# lego_motors_booster_1x4-.net
KiCad netlist of a schematic drawn in EAGLE
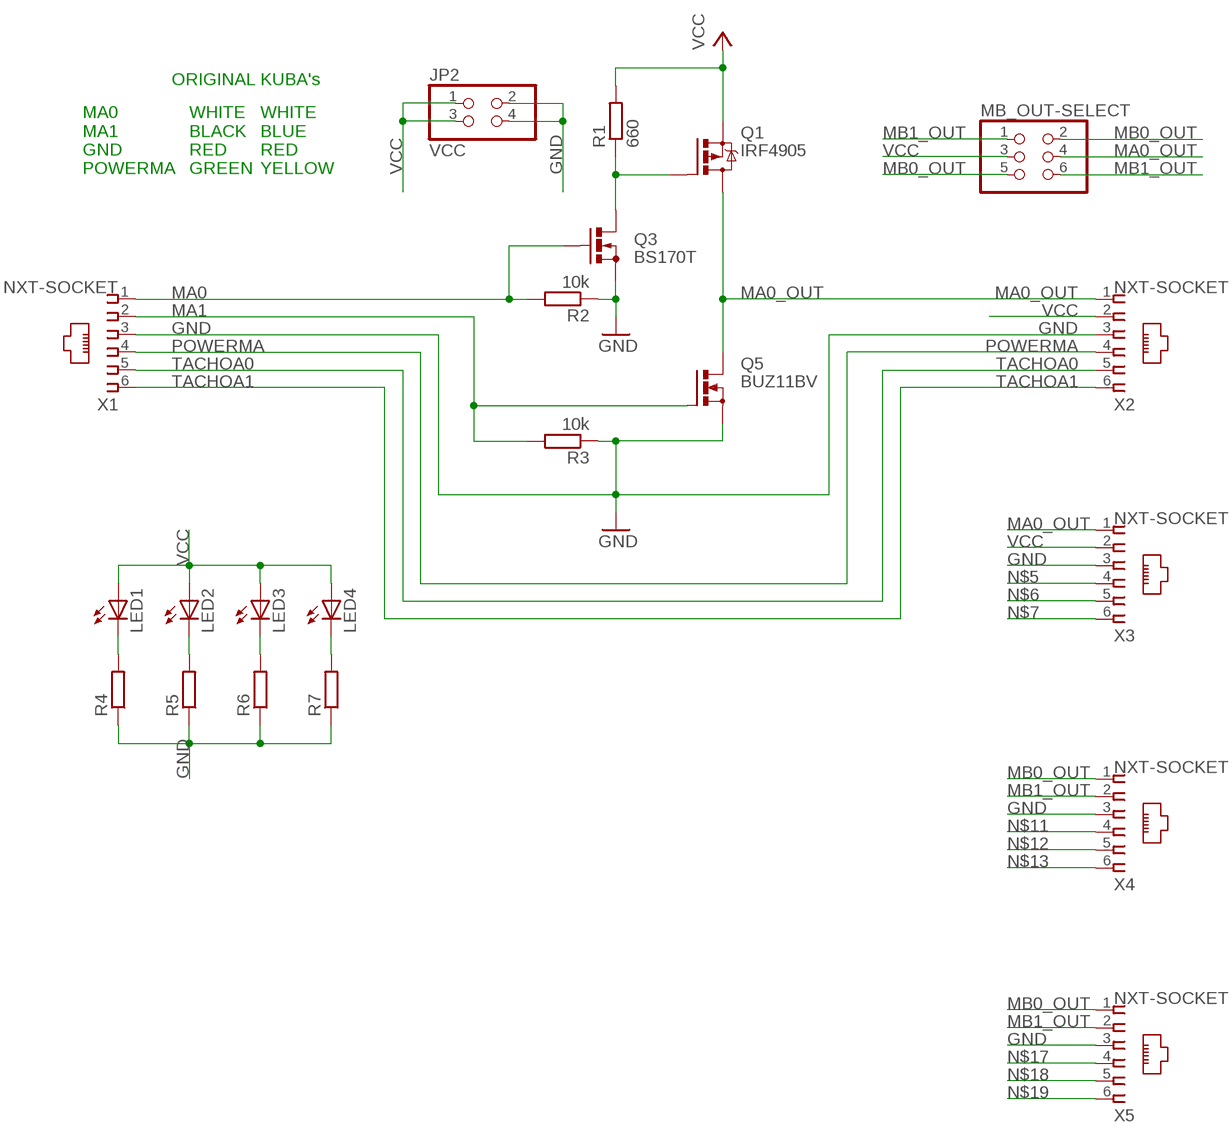
[diagram p0: schematic, sheet 1]

(export (version "E")
  (design (tool "Eeschema 10.0.6"))
  (components
    (comp (ref "JP2")
      (value "VCC")
      (footprint "eagle-import:2X02")
      (libsource (lib "eagle-import") (part "PINHD-2X2"))
    )
    (comp (ref "LED1")
      (value "LEDSML0603")
      (footprint "eagle-import:SML0603")
      (libsource (lib "eagle-import") (part "LEDSML0603"))
    )
    (comp (ref "LED2")
      (value "LEDSML0603")
      (footprint "eagle-import:SML0603")
      (libsource (lib "eagle-import") (part "LEDSML0603"))
    )
    (comp (ref "LED3")
      (value "LEDSML0603")
      (footprint "eagle-import:SML0603")
      (libsource (lib "eagle-import") (part "LEDSML0603"))
    )
    (comp (ref "LED4")
      (value "LEDSML0603")
      (footprint "eagle-import:SML0603")
      (libsource (lib "eagle-import") (part "LEDSML0603"))
    )
    (comp (ref "MB_OUT-SELECT")
      (value "PINHD-2X3")
      (footprint "eagle-import:2X03")
      (libsource (lib "eagle-import") (part "PINHD-2X3"))
    )
    (comp (ref "Q1")
      (value "IRF4905")
      (footprint "eagle-import:TO220BV")
      (libsource (lib "eagle-import") (part "IRF9530"))
    )
    (comp (ref "Q3")
      (value "BS170T")
      (footprint "eagle-import:SOT54E")
      (libsource (lib "eagle-import") (part "BS170T"))
    )
    (comp (ref "Q5")
      (value "BUZ11BV")
      (footprint "eagle-import:TO220BV")
      (libsource (lib "eagle-import") (part "BUZ11BV"))
    )
    (comp (ref "R1")
      (value "660")
      (footprint "eagle-import:0204_7")
      (libsource (lib "eagle-import") (part "R-EU_0204/7"))
    )
    (comp (ref "R2")
      (value "10k")
      (footprint "eagle-import:0204_7")
      (libsource (lib "eagle-import") (part "R-EU_0204/7"))
    )
    (comp (ref "R3")
      (value "10k")
      (footprint "eagle-import:0204_7")
      (libsource (lib "eagle-import") (part "R-EU_0204/7"))
    )
    (comp (ref "R4")
      (value "R-EU_R0603")
      (footprint "eagle-import:R0603")
      (libsource (lib "eagle-import") (part "R-EU_R0603"))
    )
    (comp (ref "R5")
      (value "R-EU_R0603")
      (footprint "eagle-import:R0603")
      (libsource (lib "eagle-import") (part "R-EU_R0603"))
    )
    (comp (ref "R6")
      (value "R-EU_R0603")
      (footprint "eagle-import:R0603")
      (libsource (lib "eagle-import") (part "R-EU_R0603"))
    )
    (comp (ref "R7")
      (value "R-EU_R0603")
      (footprint "eagle-import:R0603")
      (libsource (lib "eagle-import") (part "R-EU_R0603"))
    )
    (comp (ref "X1")
      (value "NXT-SOCKET")
      (footprint "eagle-import:NXT-SOCKET")
      (libsource (lib "eagle-import") (part "NXT-SOCKET"))
    )
    (comp (ref "X2")
      (value "NXT-SOCKET")
      (footprint "eagle-import:NXT-SOCKET")
      (libsource (lib "eagle-import") (part "NXT-SOCKET"))
    )
    (comp (ref "X3")
      (value "NXT-SOCKET")
      (footprint "eagle-import:NXT-SOCKET")
      (libsource (lib "eagle-import") (part "NXT-SOCKET"))
    )
    (comp (ref "X4")
      (value "NXT-SOCKET")
      (footprint "eagle-import:NXT-SOCKET")
      (libsource (lib "eagle-import") (part "NXT-SOCKET"))
    )
    (comp (ref "X5")
      (value "NXT-SOCKET")
      (footprint "eagle-import:NXT-SOCKET")
      (libsource (lib "eagle-import") (part "NXT-SOCKET"))
    )
  )
  (nets
    (net (code "1") (name "/MA0") (class "Default")
      (node (ref "Q3") (pin "G") (pinfunction "G_G") (pintype "passive"))
      (node (ref "R2") (pin "2") (pinfunction "2_2") (pintype "passive"))
      (node (ref "X1") (pin "1") (pinfunction "1_1") (pintype "passive"))
    )
    (net (code "2") (name "/MA0_OUT") (class "Default")
      (node (ref "MB_OUT-SELECT") (pin "4") (pinfunction "4_4") (pintype "passive"))
      (node (ref "Q1") (pin "D") (pinfunction "D_D") (pintype "passive"))
      (node (ref "Q5") (pin "D") (pinfunction "D_D") (pintype "passive"))
      (node (ref "X2") (pin "1") (pinfunction "1_1") (pintype "passive"))
      (node (ref "X3") (pin "1") (pinfunction "1_1") (pintype "passive"))
    )
    (net (code "3") (name "/MA1") (class "Default")
      (node (ref "Q5") (pin "G") (pinfunction "G_G") (pintype "passive"))
      (node (ref "R3") (pin "2") (pinfunction "2_2") (pintype "passive"))
      (node (ref "X1") (pin "2") (pinfunction "2_2") (pintype "passive"))
    )
    (net (code "4") (name "/MB0_OUT") (class "Default")
      (node (ref "MB_OUT-SELECT") (pin "2") (pinfunction "2_2") (pintype "passive"))
      (node (ref "MB_OUT-SELECT") (pin "5") (pinfunction "5_5") (pintype "passive"))
      (node (ref "X4") (pin "1") (pinfunction "1_1") (pintype "passive"))
      (node (ref "X5") (pin "1") (pinfunction "1_1") (pintype "passive"))
    )
    (net (code "5") (name "/MB1_OUT") (class "Default")
      (node (ref "MB_OUT-SELECT") (pin "1") (pinfunction "1_1") (pintype "passive"))
      (node (ref "MB_OUT-SELECT") (pin "6") (pinfunction "6_6") (pintype "passive"))
      (node (ref "X4") (pin "2") (pinfunction "2_2") (pintype "passive"))
      (node (ref "X5") (pin "2") (pinfunction "2_2") (pintype "passive"))
    )
    (net (code "6") (name "/N$5") (class "Default")
      (node (ref "X3") (pin "4") (pinfunction "4_4") (pintype "passive"))
    )
    (net (code "7") (name "/N$6") (class "Default")
      (node (ref "X3") (pin "5") (pinfunction "5_5") (pintype "passive"))
    )
    (net (code "8") (name "/N$7") (class "Default")
      (node (ref "X3") (pin "6") (pinfunction "6_6") (pintype "passive"))
    )
    (net (code "9") (name "/N$11") (class "Default")
      (node (ref "X4") (pin "4") (pinfunction "4_4") (pintype "passive"))
    )
    (net (code "10") (name "/N$12") (class "Default")
      (node (ref "X4") (pin "5") (pinfunction "5_5") (pintype "passive"))
    )
    (net (code "11") (name "/N$13") (class "Default")
      (node (ref "X4") (pin "6") (pinfunction "6_6") (pintype "passive"))
    )
    (net (code "12") (name "/N$17") (class "Default")
      (node (ref "X5") (pin "4") (pinfunction "4_4") (pintype "passive"))
    )
    (net (code "13") (name "/N$18") (class "Default")
      (node (ref "X5") (pin "5") (pinfunction "5_5") (pintype "passive"))
    )
    (net (code "14") (name "/N$19") (class "Default")
      (node (ref "X5") (pin "6") (pinfunction "6_6") (pintype "passive"))
    )
    (net (code "15") (name "/POWERMA") (class "Default")
      (node (ref "X1") (pin "4") (pinfunction "4_4") (pintype "passive"))
      (node (ref "X2") (pin "4") (pinfunction "4_4") (pintype "passive"))
    )
    (net (code "16") (name "/TACHOA0") (class "Default")
      (node (ref "X1") (pin "5") (pinfunction "5_5") (pintype "passive"))
      (node (ref "X2") (pin "5") (pinfunction "5_5") (pintype "passive"))
    )
    (net (code "17") (name "/TACHOA1") (class "Default")
      (node (ref "X1") (pin "6") (pinfunction "6_6") (pintype "passive"))
      (node (ref "X2") (pin "6") (pinfunction "6_6") (pintype "passive"))
    )
    (net (code "18") (name "GND") (class "Default")
      (node (ref "JP2") (pin "2") (pinfunction "2_2") (pintype "passive"))
      (node (ref "JP2") (pin "4") (pinfunction "4_4") (pintype "passive"))
      (node (ref "Q3") (pin "S") (pinfunction "S_S") (pintype "passive"))
      (node (ref "Q5") (pin "S") (pinfunction "S_S") (pintype "passive"))
      (node (ref "R2") (pin "1") (pinfunction "1_1") (pintype "passive"))
      (node (ref "R3") (pin "1") (pinfunction "1_1") (pintype "passive"))
      (node (ref "R4") (pin "1") (pinfunction "1_1") (pintype "passive"))
      (node (ref "R5") (pin "1") (pinfunction "1_1") (pintype "passive"))
      (node (ref "R6") (pin "1") (pinfunction "1_1") (pintype "passive"))
      (node (ref "R7") (pin "1") (pinfunction "1_1") (pintype "passive"))
      (node (ref "X1") (pin "3") (pinfunction "3_3") (pintype "passive"))
      (node (ref "X2") (pin "3") (pinfunction "3_3") (pintype "passive"))
      (node (ref "X3") (pin "3") (pinfunction "3_3") (pintype "passive"))
      (node (ref "X4") (pin "3") (pinfunction "3_3") (pintype "passive"))
      (node (ref "X5") (pin "3") (pinfunction "3_3") (pintype "passive"))
    )
    (net (code "19") (name "Net-(LED1-PadC)") (class "Default")
      (node (ref "LED1") (pin "C") (pinfunction "C_C") (pintype "passive"))
      (node (ref "R4") (pin "2") (pinfunction "2_2") (pintype "passive"))
    )
    (net (code "20") (name "Net-(LED2-PadC)") (class "Default")
      (node (ref "LED2") (pin "C") (pinfunction "C_C") (pintype "passive"))
      (node (ref "R5") (pin "2") (pinfunction "2_2") (pintype "passive"))
    )
    (net (code "21") (name "Net-(LED3-PadC)") (class "Default")
      (node (ref "LED3") (pin "C") (pinfunction "C_C") (pintype "passive"))
      (node (ref "R6") (pin "2") (pinfunction "2_2") (pintype "passive"))
    )
    (net (code "22") (name "Net-(LED4-PadC)") (class "Default")
      (node (ref "LED4") (pin "C") (pinfunction "C_C") (pintype "passive"))
      (node (ref "R7") (pin "2") (pinfunction "2_2") (pintype "passive"))
    )
    (net (code "23") (name "Net-(Q1-PadG)") (class "Default")
      (node (ref "Q1") (pin "G") (pinfunction "G_G") (pintype "passive"))
      (node (ref "Q3") (pin "D") (pinfunction "D_D") (pintype "passive"))
      (node (ref "R1") (pin "1") (pinfunction "1_1") (pintype "passive"))
    )
    (net (code "24") (name "VCC") (class "Default")
      (node (ref "JP2") (pin "1") (pinfunction "1_1") (pintype "passive"))
      (node (ref "JP2") (pin "3") (pinfunction "3_3") (pintype "passive"))
      (node (ref "LED1") (pin "A") (pinfunction "A_A") (pintype "passive"))
      (node (ref "LED2") (pin "A") (pinfunction "A_A") (pintype "passive"))
      (node (ref "LED3") (pin "A") (pinfunction "A_A") (pintype "passive"))
      (node (ref "LED4") (pin "A") (pinfunction "A_A") (pintype "passive"))
      (node (ref "MB_OUT-SELECT") (pin "3") (pinfunction "3_3") (pintype "passive"))
      (node (ref "Q1") (pin "S") (pinfunction "S_S") (pintype "passive"))
      (node (ref "R1") (pin "2") (pinfunction "2_2") (pintype "passive"))
      (node (ref "X2") (pin "2") (pinfunction "2_2") (pintype "passive"))
      (node (ref "X3") (pin "2") (pinfunction "2_2") (pintype "passive"))
    )
  )
)
